# 11_Clock_1.net
KiCad netlist of a schematic drawn in Altium Designer
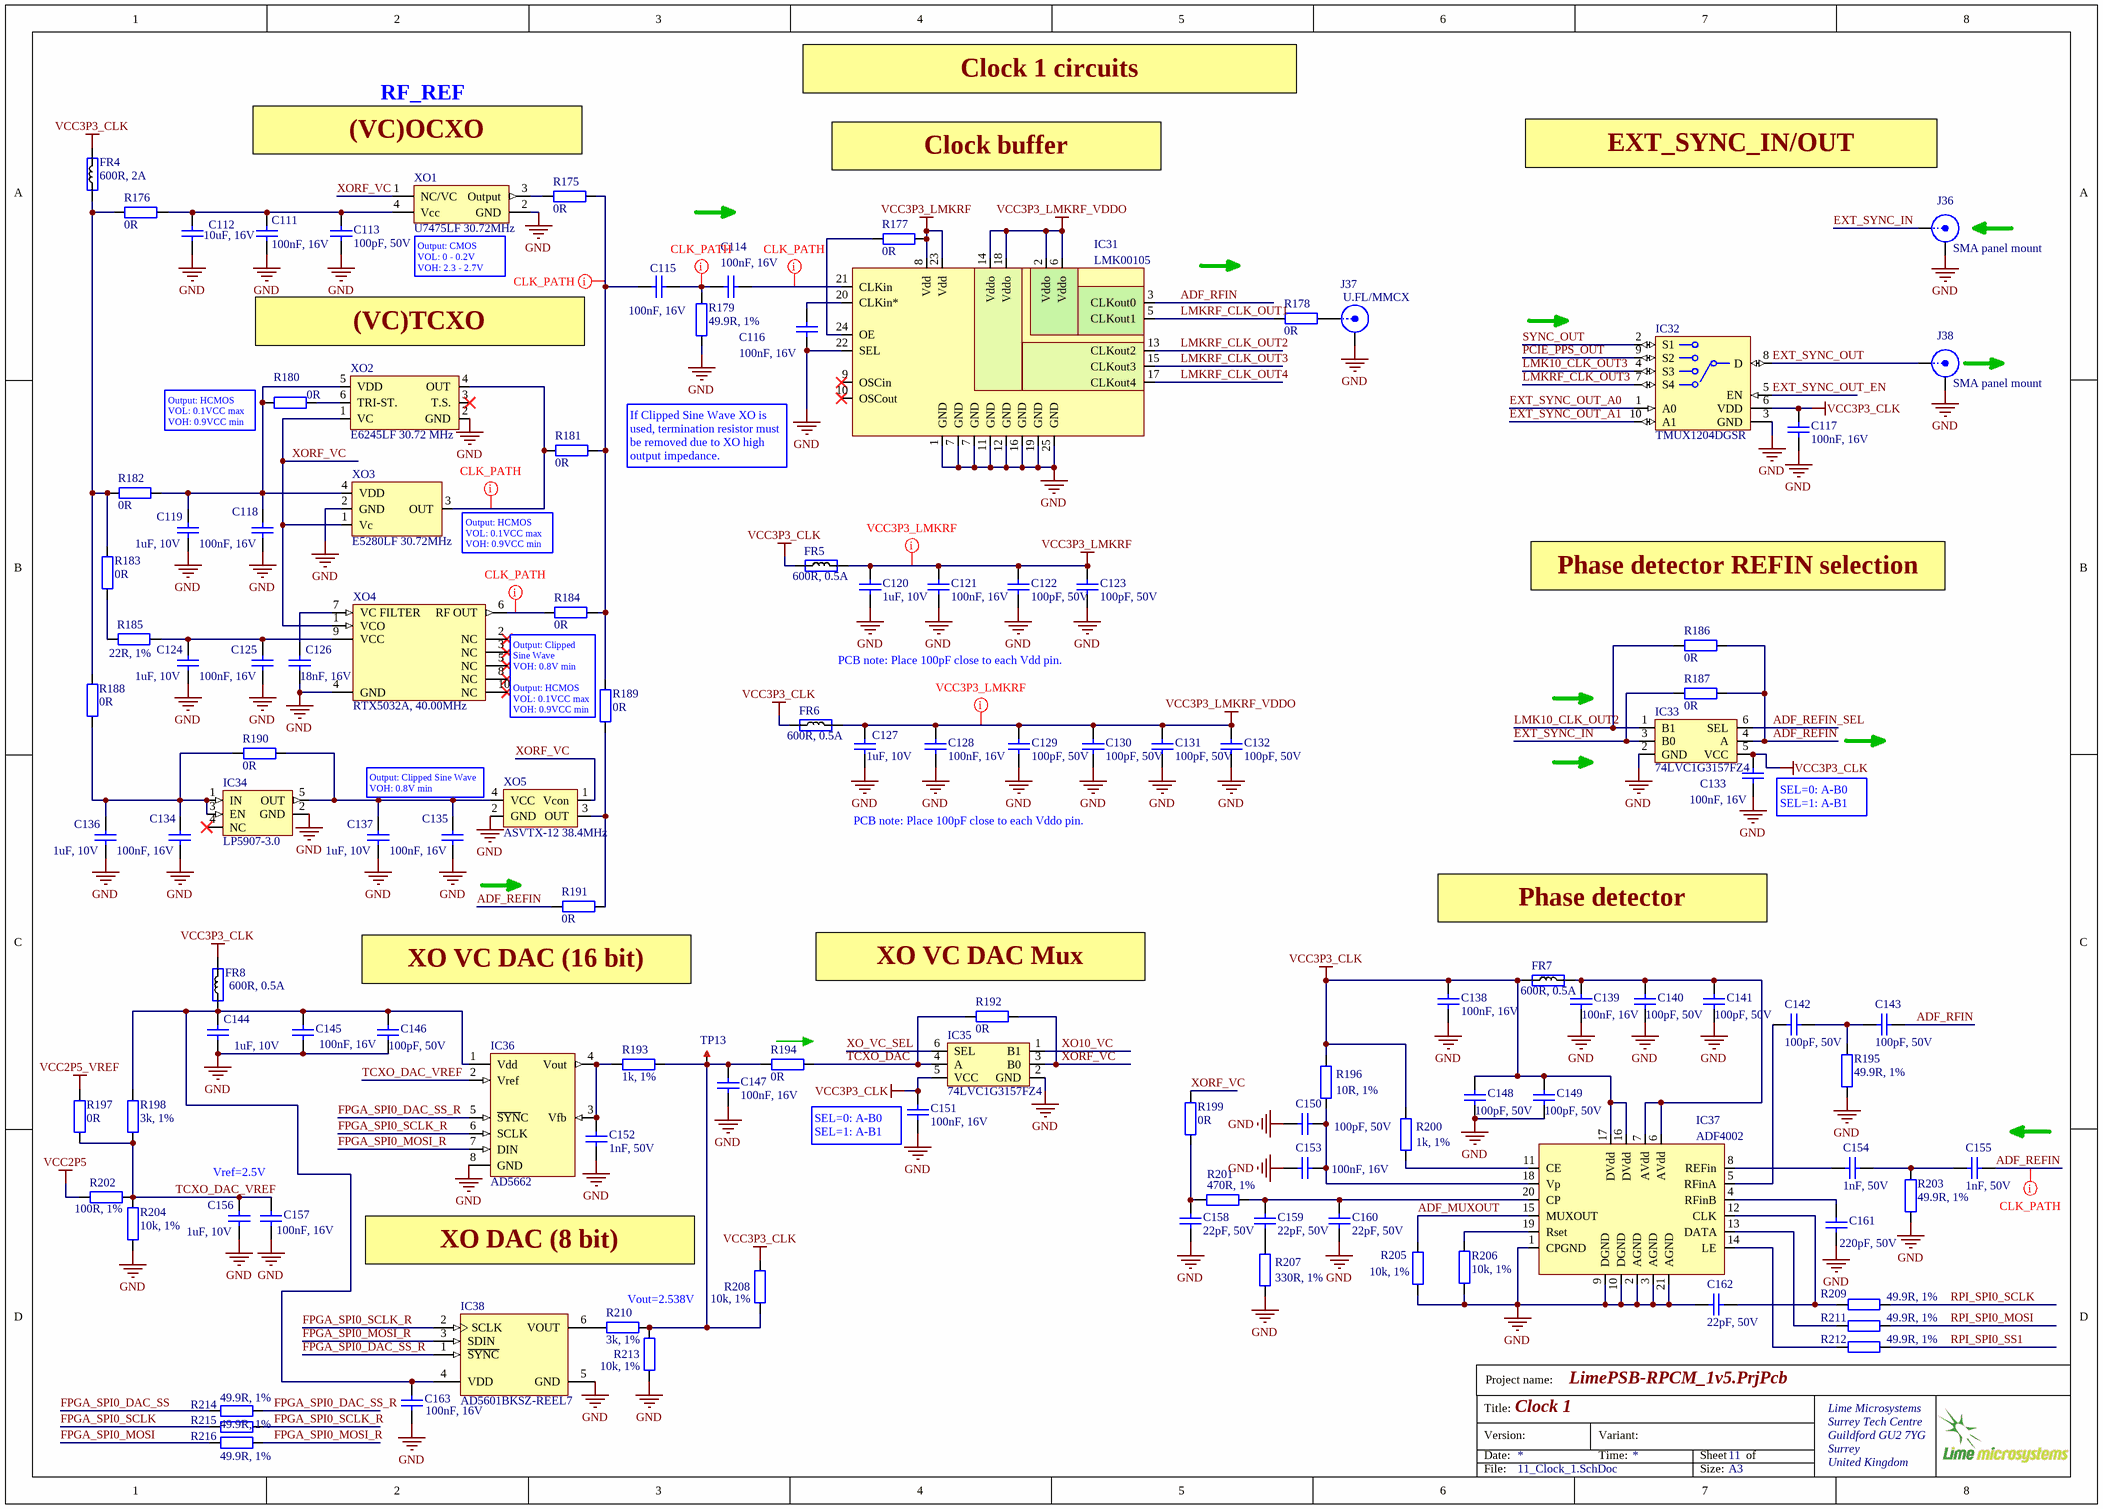
[diagram p0: 11_Clock_1.SchDoc]

(export (version "E")
  (design (tool "Eeschema 10.0.6"))
  (components
    (comp (ref "C111")
      (value "100nF, 16V")
      (footprint "CAP0402")
      (fields
        (field (name "MANUFACTURER") "Murata Electronics")
        (field (name "TOLERANCE") "10 %")
        (field (name "MANUFACTURER PART NUMBER") "GRM155R71C104KA88D")
      )
      (libsource (lib "LimeMicroAltiumLib_schLib") (part "Cap_0402"))
    )
    (comp (ref "C112")
      (value "10uF, 16V")
      (footprint "CAP0603")
      (fields (field (name "MANUFACTURER") "Yageo") (field (name "TOLERANCE") "±20%"))
      (libsource (lib "LimeMicroAltiumLib_schLib") (part "Cap_0603"))
    )
    (comp (ref "C113")
      (value "100pF, 50V")
      (footprint "CAP0402")
      (fields (field (name "TOLERANCE") "±5%") (field (name "MANUFACTURER") "Yageo"))
      (libsource (lib "LimeMicroAltiumLib_schLib") (part "Cap_0402"))
    )
    (comp (ref "C114")
      (value "100nF, 16V")
      (footprint "CAP0402")
      (fields
        (field (name "MANUFACTURER") "Murata Electronics")
        (field (name "TOLERANCE") "10 %")
        (field (name "MANUFACTURER PART NUMBER") "GRM155R71C104KA88D")
      )
      (libsource (lib "LimeMicroAltiumLib_schLib") (part "Cap_0402"))
    )
    (comp (ref "C115")
      (value "100nF, 16V")
      (footprint "CAP0402")
      (fields
        (field (name "MANUFACTURER") "Murata Electronics")
        (field (name "TOLERANCE") "10 %")
        (field (name "MANUFACTURER PART NUMBER") "GRM155R71C104KA88D")
      )
      (libsource (lib "LimeMicroAltiumLib_schLib") (part "Cap_0402"))
    )
    (comp (ref "C116")
      (value "100nF, 16V")
      (footprint "CAP0402")
      (fields
        (field (name "MANUFACTURER") "Murata Electronics")
        (field (name "TOLERANCE") "10 %")
        (field (name "MANUFACTURER PART NUMBER") "GRM155R71C104KA88D")
      )
      (libsource (lib "LimeMicroAltiumLib_schLib") (part "Cap_0402"))
    )
    (comp (ref "C117")
      (value "100nF, 16V")
      (footprint "CAP0402")
      (fields
        (field (name "MANUFACTURER") "Murata Electronics")
        (field (name "TOLERANCE") "10 %")
        (field (name "MANUFACTURER PART NUMBER") "GRM155R71C104KA88D")
      )
      (libsource (lib "LimeMicroAltiumLib_schLib") (part "Cap_0402"))
    )
    (comp (ref "C118")
      (value "100nF, 16V")
      (footprint "CAP0402")
      (fields
        (field (name "MANUFACTURER") "Murata Electronics")
        (field (name "TOLERANCE") "10 %")
        (field (name "MANUFACTURER PART NUMBER") "GRM155R71C104KA88D")
      )
      (libsource (lib "LimeMicroAltiumLib_schLib") (part "Cap_0402"))
    )
    (comp (ref "C119")
      (value "1uF, 10V")
      (footprint "CAP0402")
      (description "CAP CER 1UF 10V X5R 0402")
      (fields (field (name "MANUFACTURER") "Yageo"))
      (libsource (lib "LimeMicroAltiumLib_schLib") (part "Cap_0402"))
    )
    (comp (ref "C120")
      (value "1uF, 10V")
      (footprint "CAP0402")
      (description "CAP CER 1UF 10V X5R 0402")
      (fields (field (name "MANUFACTURER") "Yageo") (field (name "TOLERANCE") "±20%"))
      (libsource (lib "LimeMicroAltiumLib_schLib") (part "Cap_0402"))
    )
    (comp (ref "C121")
      (value "100nF, 16V")
      (footprint "CAP0402")
      (fields
        (field (name "MANUFACTURER") "Murata Electronics")
        (field (name "TOLERANCE") "10 %")
        (field (name "MANUFACTURER PART NUMBER") "GRM155R71C104KA88D")
      )
      (libsource (lib "LimeMicroAltiumLib_schLib") (part "Cap_0402"))
    )
    (comp (ref "C122")
      (value "100pF, 50V")
      (footprint "CAP0402")
      (fields (field (name "MANUFACTURER") "Yageo") (field (name "TOLERANCE") "±5%"))
      (libsource (lib "LimeMicroAltiumLib_schLib") (part "Cap_0402"))
    )
    (comp (ref "C123")
      (value "100pF, 50V")
      (footprint "CAP0402")
      (fields (field (name "MANUFACTURER") "Yageo") (field (name "TOLERANCE") "±5%"))
      (libsource (lib "LimeMicroAltiumLib_schLib") (part "Cap_0402"))
    )
    (comp (ref "C124")
      (value "1uF, 10V")
      (footprint "CAP0402")
      (description "CAP CER 1UF 10V X5R 0402")
      (fields (field (name "MANUFACTURER") "Yageo"))
      (libsource (lib "LimeMicroAltiumLib_schLib") (part "Cap_0402"))
    )
    (comp (ref "C125")
      (value "100nF, 16V")
      (footprint "CAP0402")
      (fields
        (field (name "MANUFACTURER") "Murata Electronics")
        (field (name "TOLERANCE") "10 %")
        (field (name "MANUFACTURER PART NUMBER") "GRM155R71C104KA88D")
      )
      (libsource (lib "LimeMicroAltiumLib_schLib") (part "Cap_0402"))
    )
    (comp (ref "C126")
      (value "18nF, 16V")
      (footprint "CAP0402")
      (fields (field (name "MANUFACTURER") "Yageo") (field (name "TOLERANCE") "±10%"))
      (libsource (lib "LimeMicroAltiumLib_schLib") (part "Cap_0402"))
    )
    (comp (ref "C127")
      (value "1uF, 10V")
      (footprint "CAP0402")
      (description "CAP CER 1UF 10V X5R 0402")
      (fields (field (name "MANUFACTURER") "Yageo") (field (name "TOLERANCE") "±20%"))
      (libsource (lib "LimeMicroAltiumLib_schLib") (part "Cap_0402"))
    )
    (comp (ref "C128")
      (value "100nF, 16V")
      (footprint "CAP0402")
      (fields
        (field (name "MANUFACTURER") "Murata Electronics")
        (field (name "TOLERANCE") "10 %")
        (field (name "MANUFACTURER PART NUMBER") "GRM155R71C104KA88D")
      )
      (libsource (lib "LimeMicroAltiumLib_schLib") (part "Cap_0402"))
    )
    (comp (ref "C129")
      (value "100pF, 50V")
      (footprint "CAP0402")
      (fields (field (name "MANUFACTURER") "Yageo") (field (name "TOLERANCE") "±5%"))
      (libsource (lib "LimeMicroAltiumLib_schLib") (part "Cap_0402"))
    )
    (comp (ref "C130")
      (value "100pF, 50V")
      (footprint "CAP0402")
      (fields (field (name "MANUFACTURER") "Yageo") (field (name "TOLERANCE") "±5%"))
      (libsource (lib "LimeMicroAltiumLib_schLib") (part "Cap_0402"))
    )
    (comp (ref "C131")
      (value "100pF, 50V")
      (footprint "CAP0402")
      (fields (field (name "MANUFACTURER") "Yageo") (field (name "TOLERANCE") "±5%"))
      (libsource (lib "LimeMicroAltiumLib_schLib") (part "Cap_0402"))
    )
    (comp (ref "C132")
      (value "100pF, 50V")
      (footprint "CAP0402")
      (fields (field (name "MANUFACTURER") "Yageo") (field (name "TOLERANCE") "±5%"))
      (libsource (lib "LimeMicroAltiumLib_schLib") (part "Cap_0402"))
    )
    (comp (ref "C133")
      (value "100nF, 16V")
      (footprint "CAP0402")
      (fields
        (field (name "MANUFACTURER") "Murata Electronics")
        (field (name "TOLERANCE") "10 %")
        (field (name "MANUFACTURER PART NUMBER") "GRM155R71C104KA88D")
      )
      (libsource (lib "LimeMicroAltiumLib_schLib") (part "Cap_0402"))
    )
    (comp (ref "C134")
      (value "100nF, 16V")
      (footprint "CAP0402")
      (fields
        (field (name "MANUFACTURER") "Murata Electronics")
        (field (name "TOLERANCE") "10 %")
        (field (name "MANUFACTURER PART NUMBER") "GRM155R71C104KA88D")
      )
      (libsource (lib "") (part "Cap_0402_1"))
    )
    (comp (ref "C135")
      (value "100nF, 16V")
      (footprint "CAP0402")
      (fields
        (field (name "MANUFACTURER") "Murata Electronics")
        (field (name "TOLERANCE") "10 %")
        (field (name "MANUFACTURER PART NUMBER") "GRM155R71C104KA88D")
      )
      (libsource (lib "") (part "Cap_0402_1"))
    )
    (comp (ref "C136")
      (value "1uF, 10V")
      (footprint "CAP0402")
      (fields (field (name "MANUFACTURER") "Yageo"))
      (libsource (lib "") (part "Cap_0402_1"))
    )
    (comp (ref "C137")
      (value "1uF, 10V")
      (footprint "CAP0402")
      (fields (field (name "MANUFACTURER") "Yageo"))
      (libsource (lib "") (part "Cap_0402_1"))
    )
    (comp (ref "C138")
      (value "100nF, 16V")
      (footprint "CAP0402")
      (fields
        (field (name "MANUFACTURER") "Murata Electronics")
        (field (name "TOLERANCE") "10 %")
        (field (name "MANUFACTURER PART NUMBER") "GRM155R71C104KA88D")
      )
      (libsource (lib "LimeMicroAltiumLib_schLib") (part "Cap_0402"))
    )
    (comp (ref "C139")
      (value "100nF, 16V")
      (footprint "CAP0402")
      (fields
        (field (name "MANUFACTURER") "Murata Electronics")
        (field (name "TOLERANCE") "10 %")
        (field (name "MANUFACTURER PART NUMBER") "GRM155R71C104KA88D")
      )
      (libsource (lib "LimeMicroAltiumLib_schLib") (part "Cap_0402"))
    )
    (comp (ref "C140")
      (value "100pF, 50V")
      (footprint "CAP0402")
      (fields (field (name "MANUFACTURER") "Yageo") (field (name "TOLERANCE") "±5%"))
      (libsource (lib "LimeMicroAltiumLib_schLib") (part "Cap_0402"))
    )
    (comp (ref "C141")
      (value "100pF, 50V")
      (footprint "CAP0402")
      (fields (field (name "MANUFACTURER") "Yageo") (field (name "TOLERANCE") "±5%"))
      (libsource (lib "LimeMicroAltiumLib_schLib") (part "Cap_0402"))
    )
    (comp (ref "C142")
      (value "100pF, 50V")
      (footprint "CAP0402")
      (fields (field (name "MANUFACTURER") "Yageo") (field (name "TOLERANCE") "±5%"))
      (libsource (lib "LimeMicroAltiumLib_schLib") (part "Cap_0402"))
    )
    (comp (ref "C143")
      (value "100pF, 50V")
      (footprint "CAP0402")
      (fields (field (name "MANUFACTURER") "Yageo") (field (name "TOLERANCE") "±5%"))
      (libsource (lib "LimeMicroAltiumLib_schLib") (part "Cap_0402"))
    )
    (comp (ref "C144")
      (value "1uF, 10V")
      (footprint "CAP0402")
      (description "CAP CER 1UF 10V X5R 0402")
      (fields (field (name "MANUFACTURER") "Yageo") (field (name "TOLERANCE") "±20%"))
      (libsource (lib "LimeMicroAltiumLib_schLib") (part "Cap_0402"))
    )
    (comp (ref "C145")
      (value "100nF, 16V")
      (footprint "CAP0402")
      (fields
        (field (name "TOLERANCE") "10 %")
        (field (name "MANUFACTURER") "Murata Electronics")
        (field (name "MANUFACTURER PART NUMBER") "GRM155R71C104KA88D")
      )
      (libsource (lib "LimeFPGAboard_schLib") (part "Cap_0603"))
    )
    (comp (ref "C146")
      (value "100pF, 50V")
      (footprint "CAP0402")
      (fields (field (name "MANUFACTURER") "Yageo") (field (name "TOLERANCE") "±5%"))
      (libsource (lib "LimeMicroAltiumLib_schLib") (part "Cap_0402"))
    )
    (comp (ref "C147")
      (value "100nF, 16V")
      (footprint "CAP0402")
      (fields
        (field (name "MANUFACTURER") "Murata Electronics")
        (field (name "TOLERANCE") "10 %")
        (field (name "MANUFACTURER PART NUMBER") "GRM155R71C104KA88D")
      )
      (libsource (lib "LimeMicroAltiumLib_schLib") (part "Cap_0402"))
    )
    (comp (ref "C148")
      (value "100pF, 50V")
      (footprint "CAP0402")
      (fields (field (name "MANUFACTURER") "Yageo") (field (name "TOLERANCE") "±5%"))
      (libsource (lib "LimeMicroAltiumLib_schLib") (part "Cap_0402"))
    )
    (comp (ref "C149")
      (value "100pF, 50V")
      (footprint "CAP0402")
      (fields (field (name "MANUFACTURER") "Yageo") (field (name "TOLERANCE") "±5%"))
      (libsource (lib "LimeMicroAltiumLib_schLib") (part "Cap_0402"))
    )
    (comp (ref "C150")
      (value "100pF, 50V")
      (footprint "CAP0402")
      (fields (field (name "MANUFACTURER") "Yageo") (field (name "TOLERANCE") "±5%"))
      (libsource (lib "LimeMicroAltiumLib_schLib") (part "Cap_0402"))
    )
    (comp (ref "C151")
      (value "100nF, 16V")
      (footprint "CAP0402")
      (fields
        (field (name "MANUFACTURER") "Murata Electronics")
        (field (name "TOLERANCE") "10 %")
        (field (name "MANUFACTURER PART NUMBER") "GRM155R71C104KA88D")
      )
      (libsource (lib "LimeMicroAltiumLib_schLib") (part "Cap_0402"))
    )
    (comp (ref "C152")
      (value "1nF, 50V")
      (footprint "CAP0402")
      (fields
        (field (name "TOLERANCE") "±10%")
        (field (name "MANUFACTURER") "Murata Electronics North America")
      )
      (libsource (lib "LimeMicroAltiumLib_schLib") (part "Cap_0402"))
    )
    (comp (ref "C153")
      (value "100nF, 16V")
      (footprint "CAP0402")
      (fields
        (field (name "MANUFACTURER") "Murata Electronics")
        (field (name "TOLERANCE") "10 %")
        (field (name "MANUFACTURER PART NUMBER") "GRM155R71C104KA88D")
      )
      (libsource (lib "LimeMicroAltiumLib_schLib") (part "Cap_0402"))
    )
    (comp (ref "C154")
      (value "1nF, 50V")
      (footprint "CAP0402")
      (fields
        (field (name "TOLERANCE") "±10%")
        (field (name "MANUFACTURER") "Murata Electronics North America")
      )
      (libsource (lib "LimeMicroAltiumLib_schLib") (part "Cap_0402"))
    )
    (comp (ref "C155")
      (value "1nF, 50V")
      (footprint "CAP0402")
      (fields
        (field (name "TOLERANCE") "±10%")
        (field (name "MANUFACTURER") "Murata Electronics North America")
      )
      (libsource (lib "LimeMicroAltiumLib_schLib") (part "Cap_0402"))
    )
    (comp (ref "C156")
      (value "1uF, 10V")
      (footprint "CAP0402")
      (description "CAP CER 1UF 10V X5R 0402")
      (fields (field (name "MANUFACTURER") "Yageo") (field (name "TOLERANCE") "±20%"))
      (libsource (lib "LimeMicroAltiumLib_schLib") (part "Cap_0402"))
    )
    (comp (ref "C157")
      (value "100nF, 16V")
      (footprint "CAP0402")
      (fields
        (field (name "TOLERANCE") "10 %")
        (field (name "MANUFACTURER") "Murata Electronics")
        (field (name "MANUFACTURER PART NUMBER") "GRM155R71C104KA88D")
      )
      (libsource (lib "LimeFPGAboard_schLib") (part "Cap_0603"))
    )
    (comp (ref "C158")
      (value "22pF, 50V")
      (footprint "CAP0402")
      (fields (field (name "TOLERANCE") "±5%") (field (name "MANUFACTURER") "Yageo"))
      (libsource (lib "LimeMicroAltiumLib_schLib") (part "Cap_0402"))
    )
    (comp (ref "C159")
      (value "22pF, 50V")
      (footprint "CAP0402")
      (fields (field (name "TOLERANCE") "±5%") (field (name "MANUFACTURER") "Yageo"))
      (libsource (lib "LimeMicroAltiumLib_schLib") (part "Cap_0402"))
    )
    (comp (ref "C160")
      (value "22pF, 50V")
      (footprint "CAP0402")
      (fields (field (name "TOLERANCE") "±5%") (field (name "MANUFACTURER") "Yageo"))
      (libsource (lib "LimeMicroAltiumLib_schLib") (part "Cap_0402"))
    )
    (comp (ref "C161")
      (value "220pF, 50V")
      (footprint "CAP0402")
      (fields (field (name "MANUFACTURER") "Yageo") (field (name "TOLERANCE") "±10%"))
      (libsource (lib "LimeMicroAltiumLib_schLib") (part "Cap_0402"))
    )
    (comp (ref "C162")
      (value "22pF, 50V")
      (footprint "CAP0402")
      (fields (field (name "TOLERANCE") "±5%") (field (name "MANUFACTURER") "Yageo"))
      (libsource (lib "LimeMicroAltiumLib_schLib") (part "Cap_0402"))
    )
    (comp (ref "C163")
      (value "100nF, 16V")
      (footprint "CAP0402")
      (fields
        (field (name "TOLERANCE") "10 %")
        (field (name "MANUFACTURER") "Murata Electronics")
        (field (name "MANUFACTURER PART NUMBER") "GRM155R71C104KA88D")
      )
      (libsource (lib "LimeFPGAboard_schLib") (part "Cap_0603"))
    )
    (comp (ref "FR4")
      (value "600R, 2A")
      (footprint "RES0805")
      (fields (field (name "MANUFACTURER") "TDK Corporation"))
      (libsource (lib "LimeFPGAboard_schLib") (part "Ferrite"))
    )
    (comp (ref "FR5")
      (value "600R, 0.5A")
      (footprint "RES0402")
      (fields (field (name "MANUFACTURER") "Murata") (field (name "TOLERANCE") "25%"))
      (libsource (lib "LimeMicroAltiumLib_schLib") (part "Ferrite"))
    )
    (comp (ref "FR6")
      (value "600R, 0.5A")
      (footprint "RES0402")
      (fields (field (name "MANUFACTURER") "Murata") (field (name "TOLERANCE") "25%"))
      (libsource (lib "LimeMicroAltiumLib_schLib") (part "Ferrite"))
    )
    (comp (ref "FR7")
      (value "600R, 0.5A")
      (footprint "RES0402")
      (fields (field (name "MANUFACTURER") "Murata") (field (name "TOLERANCE") "25%"))
      (libsource (lib "LimeMicroAltiumLib_schLib") (part "Ferrite"))
    )
    (comp (ref "FR8")
      (value "600R, 0.5A")
      (footprint "RES0402")
      (fields (field (name "MANUFACTURER") "Murata") (field (name "TOLERANCE") "25%"))
      (libsource (lib "LimeMicroAltiumLib_schLib") (part "Ferrite"))
    )
    (comp (ref "IC31")
      (value "LMK00105")
      (footprint "LMK00105SQ")
      (fields (field (name "MANUFACTURER") "Texas Instruments"))
      (libsource (lib "LimeMicroAltiumLib_schLib") (part "LMK00105"))
    )
    (comp (ref "IC32")
      (value "TMUX1204DGSR")
      (footprint "TMUX1204DGSR_ANALOG_SWITCH_10-TSSOP")
      (fields (field (name "MANUFACTURER") "Texas Instruments"))
      (libsource (lib "LimeMicroAltiumLib") (part "TMUX1204DGSR_ANALOG_SWITCH"))
    )
    (comp (ref "IC33")
      (value "74LVC1G3157FZ4")
      (footprint "74LVC1G3157FZ4_SPDT_SW_DFN1410-6")
      (fields (field (name "MANUFACTURER") "Diodes"))
      (libsource (lib "LimeMicroAltiumLib_schLib_r04") (part "74LVC1G3157FZ4_SPDT_SW"))
    )
    (comp (ref "IC34")
      (value "LP5907-3.0")
      (footprint "SOT23-5")
      (fields (field (name "MANUFACTURER") "Texas Instruments"))
      (libsource (lib "LimeMicroAltiumLib_schLib_r01") (part "LP5907"))
    )
    (comp (ref "IC35")
      (value "74LVC1G3157FZ4")
      (footprint "74LVC1G3157FZ4_SPDT_SW_DFN1410-6")
      (fields (field (name "MANUFACTURER") "Diodes"))
      (libsource (lib "") (part "74LVC1G3157FZ4_SPDT_SW_1"))
    )
    (comp (ref "IC36")
      (value "AD5662")
      (footprint "AD5662_SOT23-8")
      (fields (field (name "MANUFACTURER") "Analog Devices Inc."))
      (libsource (lib "LimeMicroAltiumLib_schLib") (part "AD5662"))
    )
    (comp (ref "IC37")
      (value "ADF4002")
      (footprint "ADF4002")
      (fields (field (name "MANUFACTURER") "Analog Devices Inc"))
      (libsource (lib "LimeMicroAltiumLib_schLib") (part "ADF4002"))
    )
    (comp (ref "IC38")
      (value "AD5601BKSZ-REEL7")
      (footprint "AD5601_SOT23-6")
      (fields (field (name "GENERIC PART NUMBER") "AD5601") (field (name "MANUFACTURER") "Analog Devices"))
      (libsource (lib "LimeMicroAltiumLib_schLib") (part "AD5601BKSZ-REEL7"))
    )
    (comp (ref "J36")
      (value "SMA panel mount")
      (footprint "SMA_connector_side")
      (description "CONN SMA JACK STR 50OHM EDGE MNT")
      (fields (field (name "MANUFACTURER") "Linx"))
      (libsource (lib "") (part "RF_IF_connector_1"))
    )
    (comp (ref "J37")
      (value "U.FL/MMCX")
      (footprint "MMCX_UFL_conn_u")
      (description "CONN UMC RCPT STR 50 OHM SMD")
      (fields (field (name "MANUFACTURER") "Molex, LLC"))
      (libsource (lib "LimeMicroAltiumLib_schLib") (part "RF_IF_connector"))
    )
    (comp (ref "J38")
      (value "SMA panel mount")
      (footprint "SMA_connector_side")
      (description "CONN SMA JACK STR 50OHM EDGE MNT")
      (fields (field (name "MANUFACTURER") "Linx"))
      (libsource (lib "") (part "RF_IF_connector_1"))
    )
    (comp (ref "R175")
      (value "0R")
      (footprint "RES0402_v2")
      (fields (field (name "MANUFACTURER") "Yageo") (field (name "TOLERANCE") "Jumper"))
      (libsource (lib "LimeMicroAltiumLib_schLib") (part "Res_0402"))
    )
    (comp (ref "R176")
      (value "0R")
      (footprint "RES0402")
      (fields (field (name "MANUFACTURER") "Yageo") (field (name "TOLERANCE") "Jumper"))
      (libsource (lib "LimeMicroAltiumLib_schLib") (part "Res_0402"))
    )
    (comp (ref "R177")
      (value "0R")
      (footprint "RES0402")
      (fields (field (name "MANUFACTURER") "Yageo") (field (name "TOLERANCE") "Jumper"))
      (libsource (lib "LimeMicroAltiumLib_schLib") (part "Res_0402"))
    )
    (comp (ref "R178")
      (value "0R")
      (footprint "RES0402")
      (fields (field (name "MANUFACTURER") "Yageo") (field (name "TOLERANCE") "Jumper"))
      (libsource (lib "") (part "Res_0402_1"))
    )
    (comp (ref "R179")
      (value "49.9R, 1%")
      (footprint "RES0402")
      (fields
        (field (name "TOLERANCE") "±1%")
        (field (name "MANUFACTURER") "Samsung Electro-Mechanics America, Inc.")
      )
      (libsource (lib "LimeMicroAltiumLib_schLib") (part "Res_0402"))
    )
    (comp (ref "R180")
      (value "0R")
      (footprint "RES0402")
      (fields (field (name "MANUFACTURER") "Yageo") (field (name "TOLERANCE") "Jumper"))
      (libsource (lib "LimeMicroAltiumLib_schLib") (part "Res_0402"))
    )
    (comp (ref "R181")
      (value "0R")
      (footprint "RES0402_v2")
      (fields (field (name "MANUFACTURER") "Yageo") (field (name "TOLERANCE") "Jumper"))
      (libsource (lib "LimeMicroAltiumLib_schLib") (part "Res_0402"))
    )
    (comp (ref "R182")
      (value "0R")
      (footprint "RES0402")
      (fields (field (name "MANUFACTURER") "Yageo") (field (name "TOLERANCE") "Jumper"))
      (libsource (lib "LimeMicroAltiumLib_schLib") (part "Res_0402"))
    )
    (comp (ref "R183")
      (value "0R")
      (footprint "RES0402")
      (fields (field (name "MANUFACTURER") "Yageo") (field (name "TOLERANCE") "Jumper"))
      (libsource (lib "LimeMicroAltiumLib_schLib") (part "Res_0402"))
    )
    (comp (ref "R184")
      (value "0R")
      (footprint "RES0402_v2")
      (fields (field (name "MANUFACTURER") "Yageo") (field (name "TOLERANCE") "Jumper"))
      (libsource (lib "LimeMicroAltiumLib_schLib") (part "Res_0402"))
    )
    (comp (ref "R185")
      (value "22R, 1%")
      (footprint "RES0402")
      (fields (field (name "TOLERANCE") "±1%") (field (name "MANUFACTURER") "Yageo"))
      (libsource (lib "LimeFPGAboard_schLib") (part "Res_0402"))
    )
    (comp (ref "R186")
      (value "0R")
      (footprint "RES0402_v2")
      (fields (field (name "MANUFACTURER") "Yageo") (field (name "TOLERANCE") "Jumper"))
      (libsource (lib "LimeMicroAltiumLib_schLib") (part "Res_0402"))
    )
    (comp (ref "R187")
      (value "0R")
      (footprint "RES0402_v2")
      (fields (field (name "MANUFACTURER") "Yageo") (field (name "TOLERANCE") "Jumper"))
      (libsource (lib "LimeMicroAltiumLib_schLib") (part "Res_0402"))
    )
    (comp (ref "R188")
      (value "0R")
      (footprint "RES0402")
      (fields (field (name "MANUFACTURER") "Yageo") (field (name "TOLERANCE") "Jumper"))
      (libsource (lib "") (part "Res_0402_1"))
    )
    (comp (ref "R189")
      (value "0R")
      (footprint "RES0402_v2")
      (fields (field (name "MANUFACTURER") "Yageo") (field (name "TOLERANCE") "Jumper"))
      (libsource (lib "") (part "Res_0402_1"))
    )
    (comp (ref "R190")
      (value "0R")
      (footprint "RES0402")
      (fields (field (name "MANUFACTURER") "Yageo") (field (name "TOLERANCE") "Jumper"))
      (libsource (lib "") (part "Res_0402_1"))
    )
    (comp (ref "R191")
      (value "0R")
      (footprint "RES0402_v2")
      (fields (field (name "MANUFACTURER") "Yageo") (field (name "TOLERANCE") "Jumper"))
      (libsource (lib "LimeMicroAltiumLib_schLib") (part "Res_0402"))
    )
    (comp (ref "R192")
      (value "0R")
      (footprint "RES0402_v2")
      (fields (field (name "MANUFACTURER") "Yageo") (field (name "TOLERANCE") "Jumper"))
      (libsource (lib "LimeMicroAltiumLib_schLib") (part "Res_0402"))
    )
    (comp (ref "R193")
      (value "1k, 1%")
      (footprint "RES0402")
      (fields (field (name "MANUFACTURER") "Stackpole Electronics Inc") (field (name "TOLERANCE") "±1%"))
      (libsource (lib "LimeMicroAltiumLib_schLib") (part "Res_0402"))
    )
    (comp (ref "R194")
      (value "0R")
      (footprint "RES0402")
      (fields (field (name "MANUFACTURER") "Yageo") (field (name "TOLERANCE") "Jumper"))
      (libsource (lib "LimeMicroAltiumLib_schLib") (part "Res_0402"))
    )
    (comp (ref "R195")
      (value "49.9R, 1%")
      (footprint "RES0402")
      (fields
        (field (name "TOLERANCE") "±1%")
        (field (name "MANUFACTURER") "Samsung Electro-Mechanics America, Inc.")
      )
      (libsource (lib "LimeMicroAltiumLib_schLib") (part "Res_0402"))
    )
    (comp (ref "R196")
      (value "10R, 1%")
      (footprint "RES0402")
      (fields (field (name "MANUFACTURER") "Stackpole Electronics") (field (name "TOLERANCE") "1%"))
      (libsource (lib "LimeMicroAltiumLib_schLib") (part "Res_0402"))
    )
    (comp (ref "R197")
      (value "0R")
      (footprint "RES0402_v2")
      (fields (field (name "MANUFACTURER") "Yageo") (field (name "TOLERANCE") "Jumper"))
      (libsource (lib "LimeMicroAltiumLib_schLib") (part "Res_0402"))
    )
    (comp (ref "R198")
      (value "3k, 1%")
      (footprint "RES0402")
      (fields (field (name "TOLERANCE") "±1%") (field (name "MANUFACTURER") "Vishay Dale"))
      (libsource (lib "LimeMicroAltiumLib_schLib") (part "Res_0402"))
    )
    (comp (ref "R199")
      (value "0R")
      (footprint "RES0402")
      (fields (field (name "MANUFACTURER") "Yageo") (field (name "TOLERANCE") "Jumper"))
      (libsource (lib "LimeMicroAltiumLib_schLib") (part "Res_0402"))
    )
    (comp (ref "R200")
      (value "1k, 1%")
      (footprint "RES0402")
      (fields (field (name "MANUFACTURER") "Stackpole Electronics Inc") (field (name "TOLERANCE") "±1%"))
      (libsource (lib "LimeMicroAltiumLib_schLib") (part "Res_0402"))
    )
    (comp (ref "R201")
      (value "470R, 1%")
      (footprint "RES0402")
      (fields (field (name "TOLERANCE") "1%") (field (name "MANUFACTURER") "Yageo"))
      (libsource (lib "") (part "Res_0402_1"))
    )
    (comp (ref "R202")
      (value "100R, 1%")
      (footprint "RES0402")
      (fields (field (name "TOLERANCE") "±1%") (field (name "MANUFACTURER") "Stackpole Electronics Inc."))
      (libsource (lib "LimeMicroAltiumLib_schLib") (part "Res_0402"))
    )
    (comp (ref "R203")
      (value "49.9R, 1%")
      (footprint "RES0402")
      (fields
        (field (name "TOLERANCE") "±1%")
        (field (name "MANUFACTURER") "Samsung Electro-Mechanics America, Inc.")
      )
      (libsource (lib "LimeMicroAltiumLib_schLib") (part "Res_0402"))
    )
    (comp (ref "R204")
      (value "10k, 1%")
      (footprint "RES0402")
      (fields (field (name "MANUFACTURER") "Yageo") (field (name "TOLERANCE") "±1%"))
      (libsource (lib "LimeMicroAltiumLib_schLib") (part "Res_0402"))
    )
    (comp (ref "R205")
      (value "10k, 1%")
      (footprint "RES0402")
      (fields (field (name "MANUFACTURER") "Yageo") (field (name "TOLERANCE") "±1%"))
      (libsource (lib "LimeMicroAltiumLib_schLib") (part "Res_0402"))
    )
    (comp (ref "R206")
      (value "10k, 1%")
      (footprint "RES0402")
      (fields (field (name "MANUFACTURER") "Yageo") (field (name "TOLERANCE") "±1%"))
      (libsource (lib "LimeMicroAltiumLib_schLib") (part "Res_0402"))
    )
    (comp (ref "R207")
      (value "330R, 1%")
      (footprint "RES0402")
      (fields (field (name "MANUFACTURER") "Yageo") (field (name "TOLERANCE") "1%"))
      (libsource (lib "LimeMicroAltiumLib_schLib") (part "Res_0402"))
    )
    (comp (ref "R208")
      (value "10k, 1%")
      (footprint "RES0402")
      (fields (field (name "MANUFACTURER") "Yageo") (field (name "TOLERANCE") "±1%"))
      (libsource (lib "LimeMicroAltiumLib_schLib") (part "Res_0402"))
    )
    (comp (ref "R209")
      (value "49.9R, 1%")
      (footprint "RES0402")
      (fields
        (field (name "TOLERANCE") "±1%")
        (field (name "MANUFACTURER") "Samsung Electro-Mechanics America, Inc.")
      )
      (libsource (lib "LimeMicroAltiumLib_schLib") (part "Res_0402"))
    )
    (comp (ref "R210")
      (value "3k, 1%")
      (footprint "RES0402")
      (fields (field (name "TOLERANCE") "±1%") (field (name "MANUFACTURER") "Vishay Dale"))
      (libsource (lib "LimeMicroAltiumLib_schLib") (part "Res_0402"))
    )
    (comp (ref "R211")
      (value "49.9R, 1%")
      (footprint "RES0402")
      (fields
        (field (name "TOLERANCE") "±1%")
        (field (name "MANUFACTURER") "Samsung Electro-Mechanics America, Inc.")
      )
      (libsource (lib "LimeMicroAltiumLib_schLib") (part "Res_0402"))
    )
    (comp (ref "R212")
      (value "49.9R, 1%")
      (footprint "RES0402")
      (fields
        (field (name "TOLERANCE") "±1%")
        (field (name "MANUFACTURER") "Samsung Electro-Mechanics America, Inc.")
      )
      (libsource (lib "LimeMicroAltiumLib_schLib") (part "Res_0402"))
    )
    (comp (ref "R213")
      (value "10k, 1%")
      (footprint "RES0402")
      (fields (field (name "MANUFACTURER") "Yageo") (field (name "TOLERANCE") "±1%"))
      (libsource (lib "LimeMicroAltiumLib_schLib") (part "Res_0402"))
    )
    (comp (ref "R214")
      (value "49.9R, 1%")
      (footprint "RES0402")
      (fields
        (field (name "TOLERANCE") "±1%")
        (field (name "MANUFACTURER") "Samsung Electro-Mechanics America, Inc.")
      )
      (libsource (lib "LimeMicroAltiumLib_schLib") (part "Res_0402"))
    )
    (comp (ref "R215")
      (value "49.9R, 1%")
      (footprint "RES0402")
      (fields
        (field (name "TOLERANCE") "±1%")
        (field (name "MANUFACTURER") "Samsung Electro-Mechanics America, Inc.")
      )
      (libsource (lib "LimeMicroAltiumLib_schLib") (part "Res_0402"))
    )
    (comp (ref "R216")
      (value "49.9R, 1%")
      (footprint "RES0402")
      (fields
        (field (name "TOLERANCE") "±1%")
        (field (name "MANUFACTURER") "Samsung Electro-Mechanics America, Inc.")
      )
      (libsource (lib "LimeMicroAltiumLib_schLib") (part "Res_0402"))
    )
    (comp (ref "TP13")
      (value "TESTPOINT_PAD")
      (footprint "TP_PAD_1p5MM")
      (description "Test Point PCB mount Miniature White")
      (libsource (lib "LimeMicroAltiumLib_schLib_r04") (part "TESTPOINT_PAD"))
    )
    (comp (ref "XO1")
      (value "U7475LF 30.72MHz")
      (footprint "AOCJYR-10.000MHz")
      (fields (field (name "MANUFACTURER") "Rakon"))
      (libsource (lib "LimeMicroAltiumLib_schLib") (part "AOCJYR-10.000MHz"))
    )
    (comp (ref "XO2")
      (value "E6245LF 30.72 MHz")
      (footprint "RAKON_RPT7050A")
      (fields (field (name "MANUFACTURER") "Rakon"))
      (libsource (lib "LimeMicroAltiumLib_schLib") (part "RPT7050A"))
    )
    (comp (ref "XO3")
      (value "E5280LF 30.72MHz")
      (footprint "RAKON_TXCO")
      (fields (field (name "MANUFACTURER") "Rakon"))
      (libsource (lib "LimeMicroAltiumLib_schLib") (part "TXCO"))
    )
    (comp (ref "XO4")
      (value "RTX5032A, 40.00MHz")
      (footprint "RAKON_RTX5032A")
      (fields (field (name "MANUFACTURER") "Rakon"))
      (libsource (lib "LimeMicroAltiumLib_schLib") (part "Rakon_RTX5032A"))
    )
    (comp (ref "XO5")
      (value "ASVTX-12 38.4MHz")
      (footprint "CRYSTAL_4-LCC_2P5x2P0")
      (description "Oscillator Crystal")
      (fields (field (name "MANUFACTURER") "Abracon"))
      (libsource (lib "LimeMicroAltiumLib_schLib_r01") (part "ASVTX-12-A-38.400MHZ-H10-T_CRYSTAL"))
    )
  )
  (nets
    (net (code "2") (name "/ADF_MUXOUT") (class "Default")
      (node (ref "IC37") (pin "15") (pinfunction "MUXOUT_15") (pintype "passive"))
      (node (ref "R205") (pin "1") (pinfunction "1_1") (pintype "passive"))
    )
    (net (code "3") (name "/ADF_REFIN") (class "Default")
      (node (ref "C155") (pin "2") (pinfunction "2_2") (pintype "passive"))
      (node (ref "IC33") (pin "4") (pinfunction "A_4") (pintype "passive"))
      (node (ref "R186") (pin "1") (pinfunction "1_1") (pintype "passive"))
      (node (ref "R187") (pin "1") (pinfunction "1_1") (pintype "passive"))
      (node (ref "R191") (pin "2") (pinfunction "2_2") (pintype "passive"))
    )
    (net (code "4") (name "/ADF_REFIN_SEL") (class "Default")
      (node (ref "IC33") (pin "6") (pinfunction "SEL_6") (pintype "passive"))
    )
    (net (code "5") (name "/ADF_RFIN") (class "Default")
      (node (ref "C143") (pin "2") (pinfunction "2_2") (pintype "passive"))
      (node (ref "IC31") (pin "3") (pinfunction "CLKout0_3") (pintype "passive"))
    )
    (net (code "6") (name "/EXT_SYNC_IN") (class "Default")
      (node (ref "IC33") (pin "3") (pinfunction "B0_3") (pintype "passive"))
      (node (ref "J36") (pin "1") (pinfunction "X_1") (pintype "passive"))
      (node (ref "R187") (pin "2") (pinfunction "2_2") (pintype "passive"))
    )
    (net (code "7") (name "/EXT_SYNC_OUT") (class "Default")
      (node (ref "IC32") (pin "8") (pinfunction "D_8") (pintype "bidirectional"))
      (node (ref "J38") (pin "1") (pinfunction "X_1") (pintype "passive"))
    )
    (net (code "8") (name "/EXT_SYNC_OUT_A0") (class "Default")
      (node (ref "IC32") (pin "1") (pinfunction "A0_1") (pintype "input"))
    )
    (net (code "9") (name "/EXT_SYNC_OUT_A1") (class "Default")
      (node (ref "IC32") (pin "10") (pinfunction "A1_10") (pintype "bidirectional"))
    )
    (net (code "10") (name "/EXT_SYNC_OUT_EN") (class "Default")
      (node (ref "IC32") (pin "5") (pinfunction "EN_5") (pintype "input"))
    )
    (net (code "11") (name "/FPGA_SPI0_DAC_SS") (class "Default")
      (node (ref "R214") (pin "2") (pinfunction "2_2") (pintype "passive"))
    )
    (net (code "12") (name "/FPGA_SPI0_DAC_SS_R") (class "Default")
      (node (ref "IC36") (pin "5") (pinfunction "~{SYN}C_5") (pintype "input"))
      (node (ref "IC38") (pin "1") (pinfunction "~{SYNC}_1") (pintype "input"))
      (node (ref "R214") (pin "1") (pinfunction "1_1") (pintype "passive"))
    )
    (net (code "13") (name "/FPGA_SPI0_MOSI") (class "Default")
      (node (ref "R216") (pin "2") (pinfunction "2_2") (pintype "passive"))
    )
    (net (code "14") (name "/FPGA_SPI0_MOSI_R") (class "Default")
      (node (ref "IC36") (pin "7") (pinfunction "DIN_7") (pintype "input"))
      (node (ref "IC38") (pin "3") (pinfunction "SDIN_3") (pintype "input"))
      (node (ref "R216") (pin "1") (pinfunction "1_1") (pintype "passive"))
    )
    (net (code "15") (name "/FPGA_SPI0_SCLK") (class "Default")
      (node (ref "R215") (pin "2") (pinfunction "2_2") (pintype "passive"))
    )
    (net (code "16") (name "/FPGA_SPI0_SCLK_R") (class "Default")
      (node (ref "IC36") (pin "6") (pinfunction "SCLK_6") (pintype "input"))
      (node (ref "IC38") (pin "2") (pinfunction "SCLK_2") (pintype "input"))
      (node (ref "R215") (pin "1") (pinfunction "1_1") (pintype "passive"))
    )
    (net (code "17") (name "/LMK10_CLK_OUT2") (class "Default")
      (node (ref "IC33") (pin "1") (pinfunction "B1_1") (pintype "passive"))
      (node (ref "R186") (pin "2") (pinfunction "2_2") (pintype "passive"))
    )
    (net (code "18") (name "/LMK10_CLK_OUT3") (class "Default")
      (node (ref "IC32") (pin "4") (pinfunction "S3_4") (pintype "bidirectional"))
    )
    (net (code "19") (name "/LMKRF_CLK_OUT1") (class "Default")
      (node (ref "IC31") (pin "5") (pinfunction "CLKout1_5") (pintype "passive"))
      (node (ref "R178") (pin "2") (pinfunction "2_2") (pintype "passive"))
    )
    (net (code "20") (name "/LMKRF_CLK_OUT2") (class "Default")
      (node (ref "IC31") (pin "13") (pinfunction "CLKout2_13") (pintype "passive"))
    )
    (net (code "21") (name "/LMKRF_CLK_OUT3") (class "Default")
      (node (ref "IC31") (pin "15") (pinfunction "CLKout3_15") (pintype "passive"))
      (node (ref "IC32") (pin "7") (pinfunction "S4_7") (pintype "bidirectional"))
    )
    (net (code "22") (name "/LMKRF_CLK_OUT4") (class "Default")
      (node (ref "IC31") (pin "17") (pinfunction "CLKout4_17") (pintype "passive"))
    )
    (net (code "23") (name "/PCIE_PPS_OUT") (class "Default")
      (node (ref "IC32") (pin "9") (pinfunction "S2_9") (pintype "bidirectional"))
    )
    (net (code "24") (name "/RPI_SPI0_MOSI") (class "Default")
      (node (ref "R211") (pin "1") (pinfunction "1_1") (pintype "passive"))
    )
    (net (code "25") (name "/RPI_SPI0_SCLK") (class "Default")
      (node (ref "R209") (pin "1") (pinfunction "1_1") (pintype "passive"))
    )
    (net (code "26") (name "/RPI_SPI0_SS1") (class "Default")
      (node (ref "R212") (pin "1") (pinfunction "1_1") (pintype "passive"))
    )
    (net (code "27") (name "/SYNC_OUT") (class "Default")
      (node (ref "IC32") (pin "2") (pinfunction "S1_2") (pintype "bidirectional"))
    )
    (net (code "28") (name "/TCXO_DAC") (class "Default")
      (node (ref "IC35") (pin "4") (pinfunction "A_4") (pintype "passive"))
      (node (ref "R192") (pin "2") (pinfunction "2_2") (pintype "passive"))
      (node (ref "R194") (pin "1") (pinfunction "1_1") (pintype "passive"))
    )
    (net (code "29") (name "/TCXO_DAC_VREF") (class "Default")
      (node (ref "C156") (pin "2") (pinfunction "2_2") (pintype "passive"))
      (node (ref "C157") (pin "1") (pinfunction "1_1") (pintype "passive"))
      (node (ref "IC36") (pin "2") (pinfunction "Vref_2") (pintype "input"))
      (node (ref "R197") (pin "1") (pinfunction "1_1") (pintype "passive"))
      (node (ref "R198") (pin "1") (pinfunction "1_1") (pintype "passive"))
      (node (ref "R202") (pin "1") (pinfunction "1_1") (pintype "passive"))
      (node (ref "R204") (pin "1") (pinfunction "1_1") (pintype "passive"))
    )
    (net (code "30") (name "/XO10_VC") (class "Default")
      (node (ref "IC35") (pin "1") (pinfunction "B1_1") (pintype "passive"))
    )
    (net (code "31") (name "/XORF_VC") (class "Default")
      (node (ref "IC35") (pin "3") (pinfunction "B0_3") (pintype "passive"))
      (node (ref "R192") (pin "1") (pinfunction "1_1") (pintype "passive"))
      (node (ref "R199") (pin "2") (pinfunction "2_2") (pintype "passive"))
      (node (ref "XO1") (pin "1") (pinfunction "NC/VC_1") (pintype "passive"))
      (node (ref "XO2") (pin "1") (pinfunction "VC_1") (pintype "passive"))
      (node (ref "XO3") (pin "1") (pinfunction "Vc_1") (pintype "passive"))
      (node (ref "XO4") (pin "1") (pinfunction "VCO_1") (pintype "input"))
      (node (ref "XO5") (pin "1") (pinfunction "Vcon_1") (pintype "passive"))
    )
    (net (code "32") (name "/XO_VC_SEL") (class "Default")
      (node (ref "IC35") (pin "6") (pinfunction "SEL_6") (pintype "passive"))
    )
    (net (code "33") (name "GND") (class "Default")
      (node (ref "C111") (pin "1") (pinfunction "1_1") (pintype "passive"))
      (node (ref "C112") (pin "1") (pinfunction "1_1") (pintype "passive"))
      (node (ref "C113") (pin "2") (pinfunction "2_2") (pintype "passive"))
      (node (ref "C116") (pin "1") (pinfunction "1_1") (pintype "passive"))
      (node (ref "C117") (pin "1") (pinfunction "1_1") (pintype "passive"))
      (node (ref "C118") (pin "1") (pinfunction "1_1") (pintype "passive"))
      (node (ref "C119") (pin "1") (pinfunction "1_1") (pintype "passive"))
      (node (ref "C120") (pin "1") (pinfunction "1_1") (pintype "passive"))
      (node (ref "C121") (pin "1") (pinfunction "1_1") (pintype "passive"))
      (node (ref "C122") (pin "1") (pinfunction "1_1") (pintype "passive"))
      (node (ref "C123") (pin "1") (pinfunction "1_1") (pintype "passive"))
      (node (ref "C124") (pin "1") (pinfunction "1_1") (pintype "passive"))
      (node (ref "C125") (pin "1") (pinfunction "1_1") (pintype "passive"))
      (node (ref "C126") (pin "1") (pinfunction "1_1") (pintype "passive"))
      (node (ref "C127") (pin "1") (pinfunction "1_1") (pintype "passive"))
      (node (ref "C128") (pin "1") (pinfunction "1_1") (pintype "passive"))
      (node (ref "C129") (pin "1") (pinfunction "1_1") (pintype "passive"))
      (node (ref "C130") (pin "1") (pinfunction "1_1") (pintype "passive"))
      (node (ref "C131") (pin "1") (pinfunction "1_1") (pintype "passive"))
      (node (ref "C132") (pin "1") (pinfunction "1_1") (pintype "passive"))
      (node (ref "C133") (pin "1") (pinfunction "1_1") (pintype "passive"))
      (node (ref "C134") (pin "1") (pinfunction "1_1") (pintype "passive"))
      (node (ref "C135") (pin "1") (pinfunction "1_1") (pintype "passive"))
      (node (ref "C136") (pin "1") (pinfunction "1_1") (pintype "passive"))
      (node (ref "C137") (pin "1") (pinfunction "1_1") (pintype "passive"))
      (node (ref "C138") (pin "1") (pinfunction "1_1") (pintype "passive"))
      (node (ref "C139") (pin "1") (pinfunction "1_1") (pintype "passive"))
      (node (ref "C140") (pin "2") (pinfunction "2_2") (pintype "passive"))
      (node (ref "C141") (pin "2") (pinfunction "2_2") (pintype "passive"))
      (node (ref "C144") (pin "1") (pinfunction "1_1") (pintype "passive"))
      (node (ref "C145") (pin "2") (pinfunction "2_2") (pintype "passive"))
      (node (ref "C146") (pin "2") (pinfunction "2_2") (pintype "passive"))
      (node (ref "C147") (pin "1") (pinfunction "1_1") (pintype "passive"))
      (node (ref "C148") (pin "2") (pinfunction "2_2") (pintype "passive"))
      (node (ref "C149") (pin "2") (pinfunction "2_2") (pintype "passive"))
      (node (ref "C150") (pin "1") (pinfunction "1_1") (pintype "passive"))
      (node (ref "C151") (pin "1") (pinfunction "1_1") (pintype "passive"))
      (node (ref "C152") (pin "2") (pinfunction "2_2") (pintype "passive"))
      (node (ref "C153") (pin "2") (pinfunction "2_2") (pintype "passive"))
      (node (ref "C156") (pin "1") (pinfunction "1_1") (pintype "passive"))
      (node (ref "C157") (pin "2") (pinfunction "2_2") (pintype "passive"))
      (node (ref "C158") (pin "1") (pinfunction "1_1") (pintype "passive"))
      (node (ref "C160") (pin "1") (pinfunction "1_1") (pintype "passive"))
      (node (ref "C161") (pin "2") (pinfunction "2_2") (pintype "passive"))
      (node (ref "C162") (pin "2") (pinfunction "2_2") (pintype "passive"))
      (node (ref "C163") (pin "2") (pinfunction "2_2") (pintype "passive"))
      (node (ref "IC31") (pin "1") (pinfunction "GND_1") (pintype "passive"))
      (node (ref "IC31") (pin "11") (pinfunction "GND_11") (pintype "passive"))
      (node (ref "IC31") (pin "12") (pinfunction "GND_12") (pintype "passive"))
      (node (ref "IC31") (pin "16") (pinfunction "GND_16") (pintype "passive"))
      (node (ref "IC31") (pin "19") (pinfunction "GND_19") (pintype "passive"))
      (node (ref "IC31") (pin "22") (pinfunction "SEL_22") (pintype "passive"))
      (node (ref "IC31") (pin "25") (pinfunction "GND_25") (pintype "passive"))
      (node (ref "IC31") (pin "7") (pinfunction "GND_7") (pintype "passive"))
      (node (ref "IC32") (pin "3") (pinfunction "GND_3") (pintype "passive"))
      (node (ref "IC33") (pin "2") (pinfunction "GND_2") (pintype "passive"))
      (node (ref "IC34") (pin "2") (pinfunction "GND_2") (pintype "passive"))
      (node (ref "IC35") (pin "2") (pinfunction "GND_2") (pintype "passive"))
      (node (ref "IC36") (pin "8") (pinfunction "GND_8") (pintype "passive"))
      (node (ref "IC37") (pin "1") (pinfunction "CPGND_1") (pintype "passive"))
      (node (ref "IC37") (pin "10") (pinfunction "DGND_10") (pintype "passive"))
      (node (ref "IC37") (pin "2") (pinfunction "AGND_2") (pintype "passive"))
      (node (ref "IC37") (pin "21") (pinfunction "AGND_21") (pintype "passive"))
      (node (ref "IC37") (pin "3") (pinfunction "AGND_3") (pintype "passive"))
      (node (ref "IC37") (pin "9") (pinfunction "DGND_9") (pintype "passive"))
      (node (ref "IC38") (pin "5") (pinfunction "GND_5") (pintype "power_in"))
      (node (ref "J36") (pin "2") (pinfunction "Y_2") (pintype "passive"))
      (node (ref "J37") (pin "2") (pinfunction "Y_2") (pintype "passive"))
      (node (ref "J38") (pin "2") (pinfunction "Y_2") (pintype "passive"))
      (node (ref "R179") (pin "1") (pinfunction "1_1") (pintype "passive"))
      (node (ref "R195") (pin "1") (pinfunction "1_1") (pintype "passive"))
      (node (ref "R203") (pin "1") (pinfunction "1_1") (pintype "passive"))
      (node (ref "R204") (pin "2") (pinfunction "2_2") (pintype "passive"))
      (node (ref "R205") (pin "2") (pinfunction "2_2") (pintype "passive"))
      (node (ref "R206") (pin "2") (pinfunction "2_2") (pintype "passive"))
      (node (ref "R207") (pin "1") (pinfunction "1_1") (pintype "passive"))
      (node (ref "R213") (pin "2") (pinfunction "2_2") (pintype "passive"))
      (node (ref "XO1") (pin "2") (pinfunction "GND_2") (pintype "passive"))
      (node (ref "XO2") (pin "2") (pinfunction "GND_2") (pintype "passive"))
      (node (ref "XO3") (pin "2") (pinfunction "GND_2") (pintype "passive"))
      (node (ref "XO4") (pin "4") (pinfunction "GND_4") (pintype "passive"))
      (node (ref "XO5") (pin "2") (pinfunction "GND_2") (pintype "passive"))
    )
    (net (code "34") (name "Net-(C114-Pad2)") (class "Default")
      (node (ref "C114") (pin "2") (pinfunction "2_2") (pintype "passive"))
      (node (ref "C115") (pin "1") (pinfunction "1_1") (pintype "passive"))
      (node (ref "R179") (pin "2") (pinfunction "2_2") (pintype "passive"))
    )
    (net (code "35") (name "Net-(C115-Pad2)") (class "Default")
      (node (ref "C115") (pin "2") (pinfunction "2_2") (pintype "passive"))
      (node (ref "R175") (pin "1") (pinfunction "1_1") (pintype "passive"))
      (node (ref "R181") (pin "1") (pinfunction "1_1") (pintype "passive"))
      (node (ref "R184") (pin "2") (pinfunction "2_2") (pintype "passive"))
      (node (ref "R189") (pin "1") (pinfunction "1_1") (pintype "passive"))
    )
    (net (code "36") (name "Net-(C139-Pad2)") (class "Default")
      (node (ref "C139") (pin "2") (pinfunction "2_2") (pintype "passive"))
      (node (ref "C140") (pin "1") (pinfunction "1_1") (pintype "passive"))
      (node (ref "C141") (pin "1") (pinfunction "1_1") (pintype "passive"))
      (node (ref "FR7") (pin "2") (pinfunction "2_2") (pintype "passive"))
      (node (ref "IC37") (pin "6") (pinfunction "AVdd_6") (pintype "passive"))
      (node (ref "IC37") (pin "7") (pinfunction "AVdd_7") (pintype "passive"))
    )
    (net (code "37") (name "Net-(C142-Pad2)") (class "Default")
      (node (ref "C142") (pin "2") (pinfunction "2_2") (pintype "passive"))
      (node (ref "C143") (pin "1") (pinfunction "1_1") (pintype "passive"))
      (node (ref "R195") (pin "2") (pinfunction "2_2") (pintype "passive"))
    )
    (net (code "38") (name "Net-(C147-Pad2)") (class "Default")
      (node (ref "C147") (pin "2") (pinfunction "2_2") (pintype "passive"))
      (node (ref "R193") (pin "1") (pinfunction "1_1") (pintype "passive"))
      (node (ref "R194") (pin "2") (pinfunction "2_2") (pintype "passive"))
      (node (ref "R208") (pin "2") (pinfunction "2_2") (pintype "passive"))
      (node (ref "R210") (pin "1") (pinfunction "1_1") (pintype "passive"))
      (node (ref "R213") (pin "1") (pinfunction "1_1") (pintype "passive"))
      (node (ref "TP13") (pin "1") (pintype "passive"))
    )
    (net (code "39") (name "Net-(C154-Pad2)") (class "Default")
      (node (ref "C154") (pin "2") (pinfunction "2_2") (pintype "passive"))
      (node (ref "C155") (pin "1") (pinfunction "1_1") (pintype "passive"))
      (node (ref "R203") (pin "2") (pinfunction "2_2") (pintype "passive"))
    )
    (net (code "40") (name "Net-(C158-Pad2)") (class "Default")
      (node (ref "C158") (pin "2") (pinfunction "2_2") (pintype "passive"))
      (node (ref "R199") (pin "1") (pinfunction "1_1") (pintype "passive"))
      (node (ref "R201") (pin "2") (pinfunction "2_2") (pintype "passive"))
    )
    (net (code "41") (name "Net-(C159-Pad1)") (class "Default")
      (node (ref "C159") (pin "1") (pinfunction "1_1") (pintype "passive"))
      (node (ref "R207") (pin "2") (pinfunction "2_2") (pintype "passive"))
    )
    (net (code "42") (name "Net-(FR4-Pad2)") (class "Default")
      (node (ref "FR4") (pin "2") (pinfunction "2_2") (pintype "passive"))
      (node (ref "R176") (pin "1") (pinfunction "1_1") (pintype "passive"))
      (node (ref "R182") (pin "2") (pinfunction "2_2") (pintype "passive"))
      (node (ref "R183") (pin "1") (pinfunction "1_1") (pintype "passive"))
      (node (ref "R188") (pin "1") (pinfunction "1_1") (pintype "passive"))
    )
    (net (code "43") (name "Net-(IC31-CLKin)") (class "Default")
      (node (ref "C114") (pin "1") (pinfunction "1_1") (pintype "passive"))
      (node (ref "IC31") (pin "21") (pinfunction "CLKin_21") (pintype "passive"))
    )
    (net (code "44") (name "Net-(IC31-CLKin*)") (class "Default")
      (node (ref "C116") (pin "2") (pinfunction "2_2") (pintype "passive"))
      (node (ref "IC31") (pin "20") (pinfunction "CLKin*_20") (pintype "passive"))
    )
    (net (code "45") (name "Net-(IC31-OE)") (class "Default")
      (node (ref "IC31") (pin "24") (pinfunction "OE_24") (pintype "passive"))
      (node (ref "R177") (pin "1") (pinfunction "1_1") (pintype "passive"))
    )
    (net (code "46") (name "Net-(IC34-EN)") (class "Default")
      (node (ref "C134") (pin "2") (pinfunction "2_2") (pintype "passive"))
      (node (ref "C136") (pin "2") (pinfunction "2_2") (pintype "passive"))
      (node (ref "IC34") (pin "1") (pinfunction "IN_1") (pintype "input"))
      (node (ref "IC34") (pin "3") (pinfunction "EN_3") (pintype "input"))
      (node (ref "R188") (pin "2") (pinfunction "2_2") (pintype "passive"))
      (node (ref "R190") (pin "2") (pinfunction "2_2") (pintype "passive"))
    )
    (net (code "47") (name "Net-(IC34-OUT)") (class "Default")
      (node (ref "C135") (pin "2") (pinfunction "2_2") (pintype "passive"))
      (node (ref "C137") (pin "2") (pinfunction "2_2") (pintype "passive"))
      (node (ref "IC34") (pin "5") (pinfunction "OUT_5") (pintype "output"))
      (node (ref "R190") (pin "1") (pinfunction "1_1") (pintype "passive"))
      (node (ref "XO5") (pin "4") (pinfunction "VCC_4") (pintype "passive"))
    )
    (net (code "48") (name "Net-(IC36-Vdd)") (class "Default")
      (node (ref "C144") (pin "2") (pinfunction "2_2") (pintype "passive"))
      (node (ref "C145") (pin "1") (pinfunction "1_1") (pintype "passive"))
      (node (ref "C146") (pin "1") (pinfunction "1_1") (pintype "passive"))
      (node (ref "C163") (pin "1") (pinfunction "1_1") (pintype "passive"))
      (node (ref "FR8") (pin "1") (pinfunction "1_1") (pintype "passive"))
      (node (ref "IC36") (pin "1") (pinfunction "Vdd_1") (pintype "power_in"))
      (node (ref "IC38") (pin "4") (pinfunction "VDD_4") (pintype "power_in"))
      (node (ref "R198") (pin "2") (pinfunction "2_2") (pintype "passive"))
    )
    (net (code "49") (name "Net-(IC36-Vfb)") (class "Default")
      (node (ref "C152") (pin "1") (pinfunction "1_1") (pintype "passive"))
      (node (ref "IC36") (pin "3") (pinfunction "Vfb_3") (pintype "input"))
      (node (ref "IC36") (pin "4") (pinfunction "Vout_4") (pintype "output"))
      (node (ref "R193") (pin "2") (pinfunction "2_2") (pintype "passive"))
    )
    (net (code "50") (name "Net-(IC37-CE)") (class "Default")
      (node (ref "IC37") (pin "11") (pinfunction "CE_11") (pintype "passive"))
      (node (ref "R200") (pin "1") (pinfunction "1_1") (pintype "passive"))
    )
    (net (code "51") (name "Net-(IC37-CLK)") (class "Default")
      (node (ref "C162") (pin "1") (pinfunction "1_1") (pintype "passive"))
      (node (ref "IC37") (pin "12") (pinfunction "CLK_12") (pintype "passive"))
      (node (ref "R209") (pin "2") (pinfunction "2_2") (pintype "passive"))
    )
    (net (code "52") (name "Net-(IC37-CP)") (class "Default")
      (node (ref "C159") (pin "2") (pinfunction "2_2") (pintype "passive"))
      (node (ref "C160") (pin "2") (pinfunction "2_2") (pintype "passive"))
      (node (ref "IC37") (pin "20") (pinfunction "CP_20") (pintype "passive"))
      (node (ref "R201") (pin "1") (pinfunction "1_1") (pintype "passive"))
    )
    (net (code "53") (name "Net-(IC37-DATA)") (class "Default")
      (node (ref "IC37") (pin "13") (pinfunction "DATA_13") (pintype "passive"))
      (node (ref "R211") (pin "2") (pinfunction "2_2") (pintype "passive"))
    )
    (net (code "54") (name "Net-(IC37-LE)") (class "Default")
      (node (ref "IC37") (pin "14") (pinfunction "LE_14") (pintype "passive"))
      (node (ref "R212") (pin "2") (pinfunction "2_2") (pintype "passive"))
    )
    (net (code "55") (name "Net-(IC37-REFin)") (class "Default")
      (node (ref "C154") (pin "1") (pinfunction "1_1") (pintype "passive"))
      (node (ref "IC37") (pin "8") (pinfunction "REFin_8") (pintype "passive"))
    )
    (net (code "56") (name "Net-(IC37-RFinA)") (class "Default")
      (node (ref "C142") (pin "1") (pinfunction "1_1") (pintype "passive"))
      (node (ref "IC37") (pin "5") (pinfunction "RFinA_5") (pintype "passive"))
    )
    (net (code "57") (name "Net-(IC37-RFinB)") (class "Default")
      (node (ref "C161") (pin "1") (pinfunction "1_1") (pintype "passive"))
      (node (ref "IC37") (pin "4") (pinfunction "RFinB_4") (pintype "passive"))
    )
    (net (code "58") (name "Net-(IC37-Rset)") (class "Default")
      (node (ref "IC37") (pin "19") (pinfunction "Rset_19") (pintype "passive"))
      (node (ref "R206") (pin "1") (pinfunction "1_1") (pintype "passive"))
    )
    (net (code "59") (name "Net-(IC37-Vp)") (class "Default")
      (node (ref "C150") (pin "2") (pinfunction "2_2") (pintype "passive"))
      (node (ref "C153") (pin "1") (pinfunction "1_1") (pintype "passive"))
      (node (ref "IC37") (pin "18") (pinfunction "Vp_18") (pintype "passive"))
      (node (ref "R196") (pin "1") (pinfunction "1_1") (pintype "passive"))
    )
    (net (code "60") (name "Net-(IC38-VOUT)") (class "Default")
      (node (ref "IC38") (pin "6") (pinfunction "VOUT_6") (pintype "tri_state"))
      (node (ref "R210") (pin "2") (pinfunction "2_2") (pintype "passive"))
    )
    (net (code "61") (name "Net-(J37-X)") (class "Default")
      (node (ref "J37") (pin "1") (pinfunction "X_1") (pintype "passive"))
      (node (ref "R178") (pin "1") (pinfunction "1_1") (pintype "passive"))
    )
    (net (code "62") (name "Net-(R183-Pad2)") (class "Default")
      (node (ref "R183") (pin "2") (pinfunction "2_2") (pintype "passive"))
      (node (ref "R185") (pin "1") (pinfunction "1_1") (pintype "passive"))
    )
    (net (code "63") (name "Net-(XO1-Output)") (class "Default")
      (node (ref "R175") (pin "2") (pinfunction "2_2") (pintype "passive"))
      (node (ref "XO1") (pin "3") (pinfunction "Output_3") (pintype "output"))
    )
    (net (code "64") (name "Net-(XO1-Vcc)") (class "Default")
      (node (ref "C111") (pin "2") (pinfunction "2_2") (pintype "passive"))
      (node (ref "C112") (pin "2") (pinfunction "2_2") (pintype "passive"))
      (node (ref "C113") (pin "1") (pinfunction "1_1") (pintype "passive"))
      (node (ref "R176") (pin "2") (pinfunction "2_2") (pintype "passive"))
      (node (ref "XO1") (pin "4") (pinfunction "Vcc_4") (pintype "power_in"))
    )
    (net (code "65") (name "Net-(XO2-OUT)") (class "Default")
      (node (ref "R181") (pin "2") (pinfunction "2_2") (pintype "passive"))
      (node (ref "XO2") (pin "4") (pinfunction "OUT_4") (pintype "passive"))
      (node (ref "XO3") (pin "3") (pinfunction "OUT_3") (pintype "passive"))
    )
    (net (code "66") (name "Net-(XO2-TRI-ST.)") (class "Default")
      (node (ref "R180") (pin "1") (pinfunction "1_1") (pintype "passive"))
      (node (ref "XO2") (pin "6") (pinfunction "TRI-ST._6") (pintype "passive"))
    )
    (net (code "67") (name "Net-(XO2-VDD)") (class "Default")
      (node (ref "C118") (pin "2") (pinfunction "2_2") (pintype "passive"))
      (node (ref "C119") (pin "2") (pinfunction "2_2") (pintype "passive"))
      (node (ref "R180") (pin "2") (pinfunction "2_2") (pintype "passive"))
      (node (ref "R182") (pin "1") (pinfunction "1_1") (pintype "passive"))
      (node (ref "XO2") (pin "5") (pinfunction "VDD_5") (pintype "passive"))
      (node (ref "XO3") (pin "4") (pinfunction "VDD_4") (pintype "passive"))
    )
    (net (code "68") (name "Net-(XO4-RF_OUT)") (class "Default")
      (node (ref "R184") (pin "1") (pinfunction "1_1") (pintype "passive"))
      (node (ref "XO4") (pin "6") (pinfunction "RF_OUT_6") (pintype "output"))
    )
    (net (code "69") (name "Net-(XO4-VCC)") (class "Default")
      (node (ref "C124") (pin "2") (pinfunction "2_2") (pintype "passive"))
      (node (ref "C125") (pin "2") (pinfunction "2_2") (pintype "passive"))
      (node (ref "R185") (pin "2") (pinfunction "2_2") (pintype "passive"))
      (node (ref "XO4") (pin "9") (pinfunction "VCC_9") (pintype "power_in"))
    )
    (net (code "70") (name "Net-(XO4-VC_FILTER)") (class "Default")
      (node (ref "C126") (pin "2") (pinfunction "2_2") (pintype "passive"))
      (node (ref "XO4") (pin "7") (pinfunction "VC_FILTER_7") (pintype "input"))
    )
    (net (code "71") (name "Net-(XO5-OUT)") (class "Default")
      (node (ref "R189") (pin "2") (pinfunction "2_2") (pintype "passive"))
      (node (ref "R191") (pin "1") (pinfunction "1_1") (pintype "passive"))
      (node (ref "XO5") (pin "3") (pinfunction "OUT_3") (pintype "passive"))
    )
    (net (code "72") (name "VCC2P5") (class "Default")
      (node (ref "R202") (pin "2") (pinfunction "2_2") (pintype "passive"))
    )
    (net (code "73") (name "VCC2P5_VREF") (class "Default")
      (node (ref "R197") (pin "2") (pinfunction "2_2") (pintype "passive"))
    )
    (net (code "74") (name "VCC3P3_CLK") (class "Default")
      (node (ref "C117") (pin "2") (pinfunction "2_2") (pintype "passive"))
      (node (ref "C133") (pin "2") (pinfunction "2_2") (pintype "passive"))
      (node (ref "C138") (pin "2") (pinfunction "2_2") (pintype "passive"))
      (node (ref "C148") (pin "1") (pinfunction "1_1") (pintype "passive"))
      (node (ref "C149") (pin "1") (pinfunction "1_1") (pintype "passive"))
      (node (ref "C151") (pin "2") (pinfunction "2_2") (pintype "passive"))
      (node (ref "FR4") (pin "1") (pinfunction "1_1") (pintype "passive"))
      (node (ref "FR5") (pin "1") (pinfunction "1_1") (pintype "passive"))
      (node (ref "FR6") (pin "1") (pinfunction "1_1") (pintype "passive"))
      (node (ref "FR7") (pin "1") (pinfunction "1_1") (pintype "passive"))
      (node (ref "FR8") (pin "2") (pinfunction "2_2") (pintype "passive"))
      (node (ref "IC32") (pin "6") (pinfunction "VDD_6") (pintype "power_in"))
      (node (ref "IC33") (pin "5") (pinfunction "VCC_5") (pintype "passive"))
      (node (ref "IC35") (pin "5") (pinfunction "VCC_5") (pintype "passive"))
      (node (ref "IC37") (pin "16") (pinfunction "DVdd_16") (pintype "passive"))
      (node (ref "IC37") (pin "17") (pinfunction "DVdd_17") (pintype "passive"))
      (node (ref "R196") (pin "2") (pinfunction "2_2") (pintype "passive"))
      (node (ref "R200") (pin "2") (pinfunction "2_2") (pintype "passive"))
      (node (ref "R208") (pin "1") (pinfunction "1_1") (pintype "passive"))
    )
    (net (code "75") (name "VCC3P3_LMKRF") (class "Default")
      (node (ref "C120") (pin "2") (pinfunction "2_2") (pintype "passive"))
      (node (ref "C121") (pin "2") (pinfunction "2_2") (pintype "passive"))
      (node (ref "C122") (pin "2") (pinfunction "2_2") (pintype "passive"))
      (node (ref "C123") (pin "2") (pinfunction "2_2") (pintype "passive"))
      (node (ref "FR5") (pin "2") (pinfunction "2_2") (pintype "passive"))
      (node (ref "IC31") (pin "23") (pinfunction "Vdd_23") (pintype "passive"))
      (node (ref "IC31") (pin "8") (pinfunction "Vdd_8") (pintype "passive"))
      (node (ref "R177") (pin "2") (pinfunction "2_2") (pintype "passive"))
    )
    (net (code "76") (name "VCC3P3_LMKRF_VDDO") (class "Default")
      (node (ref "C127") (pin "2") (pinfunction "2_2") (pintype "passive"))
      (node (ref "C128") (pin "2") (pinfunction "2_2") (pintype "passive"))
      (node (ref "C129") (pin "2") (pinfunction "2_2") (pintype "passive"))
      (node (ref "C130") (pin "2") (pinfunction "2_2") (pintype "passive"))
      (node (ref "C131") (pin "2") (pinfunction "2_2") (pintype "passive"))
      (node (ref "C132") (pin "2") (pinfunction "2_2") (pintype "passive"))
      (node (ref "FR6") (pin "2") (pinfunction "2_2") (pintype "passive"))
      (node (ref "IC31") (pin "14") (pinfunction "Vddo_14") (pintype "passive"))
      (node (ref "IC31") (pin "18") (pinfunction "Vddo_18") (pintype "passive"))
      (node (ref "IC31") (pin "2") (pinfunction "Vddo_2") (pintype "passive"))
      (node (ref "IC31") (pin "6") (pinfunction "Vddo_6") (pintype "passive"))
    )
    (net (code "77") (name "unconnected-(IC31-OSCin-Pad9)") (class "Default")
      (node (ref "IC31") (pin "9") (pinfunction "OSCin_9") (pintype "passive+no_connect"))
    )
    (net (code "78") (name "unconnected-(IC31-OSCout-Pad10)") (class "Default")
      (node (ref "IC31") (pin "10") (pinfunction "OSCout_10") (pintype "passive+no_connect"))
    )
    (net (code "79") (name "unconnected-(IC34-NC-Pad4)") (class "Default")
      (node (ref "IC34") (pin "4") (pinfunction "NC_4") (pintype "passive+no_connect"))
    )
    (net (code "80") (name "unconnected-(XO2-T.S.-Pad3)") (class "Default")
      (node (ref "XO2") (pin "3") (pinfunction "T.S._3") (pintype "passive+no_connect"))
    )
    (net (code "81") (name "unconnected-(XO4-NC-Pad2)") (class "Default")
      (node (ref "XO4") (pin "2") (pinfunction "NC_2") (pintype "passive+no_connect"))
    )
    (net (code "82") (name "unconnected-(XO4-NC-Pad3)") (class "Default")
      (node (ref "XO4") (pin "3") (pinfunction "NC_3") (pintype "passive+no_connect"))
    )
    (net (code "83") (name "unconnected-(XO4-NC-Pad5)") (class "Default")
      (node (ref "XO4") (pin "5") (pinfunction "NC_5") (pintype "passive+no_connect"))
    )
    (net (code "84") (name "unconnected-(XO4-NC-Pad8)") (class "Default")
      (node (ref "XO4") (pin "8") (pinfunction "NC_8") (pintype "passive+no_connect"))
    )
    (net (code "85") (name "unconnected-(XO4-NC-Pad10)") (class "Default")
      (node (ref "XO4") (pin "10") (pinfunction "NC_10") (pintype "passive+no_connect"))
    )
  )
)
